# pcb_telemetria_jlcpcb.net
KiCad netlist of a schematic drawn in EAGLE
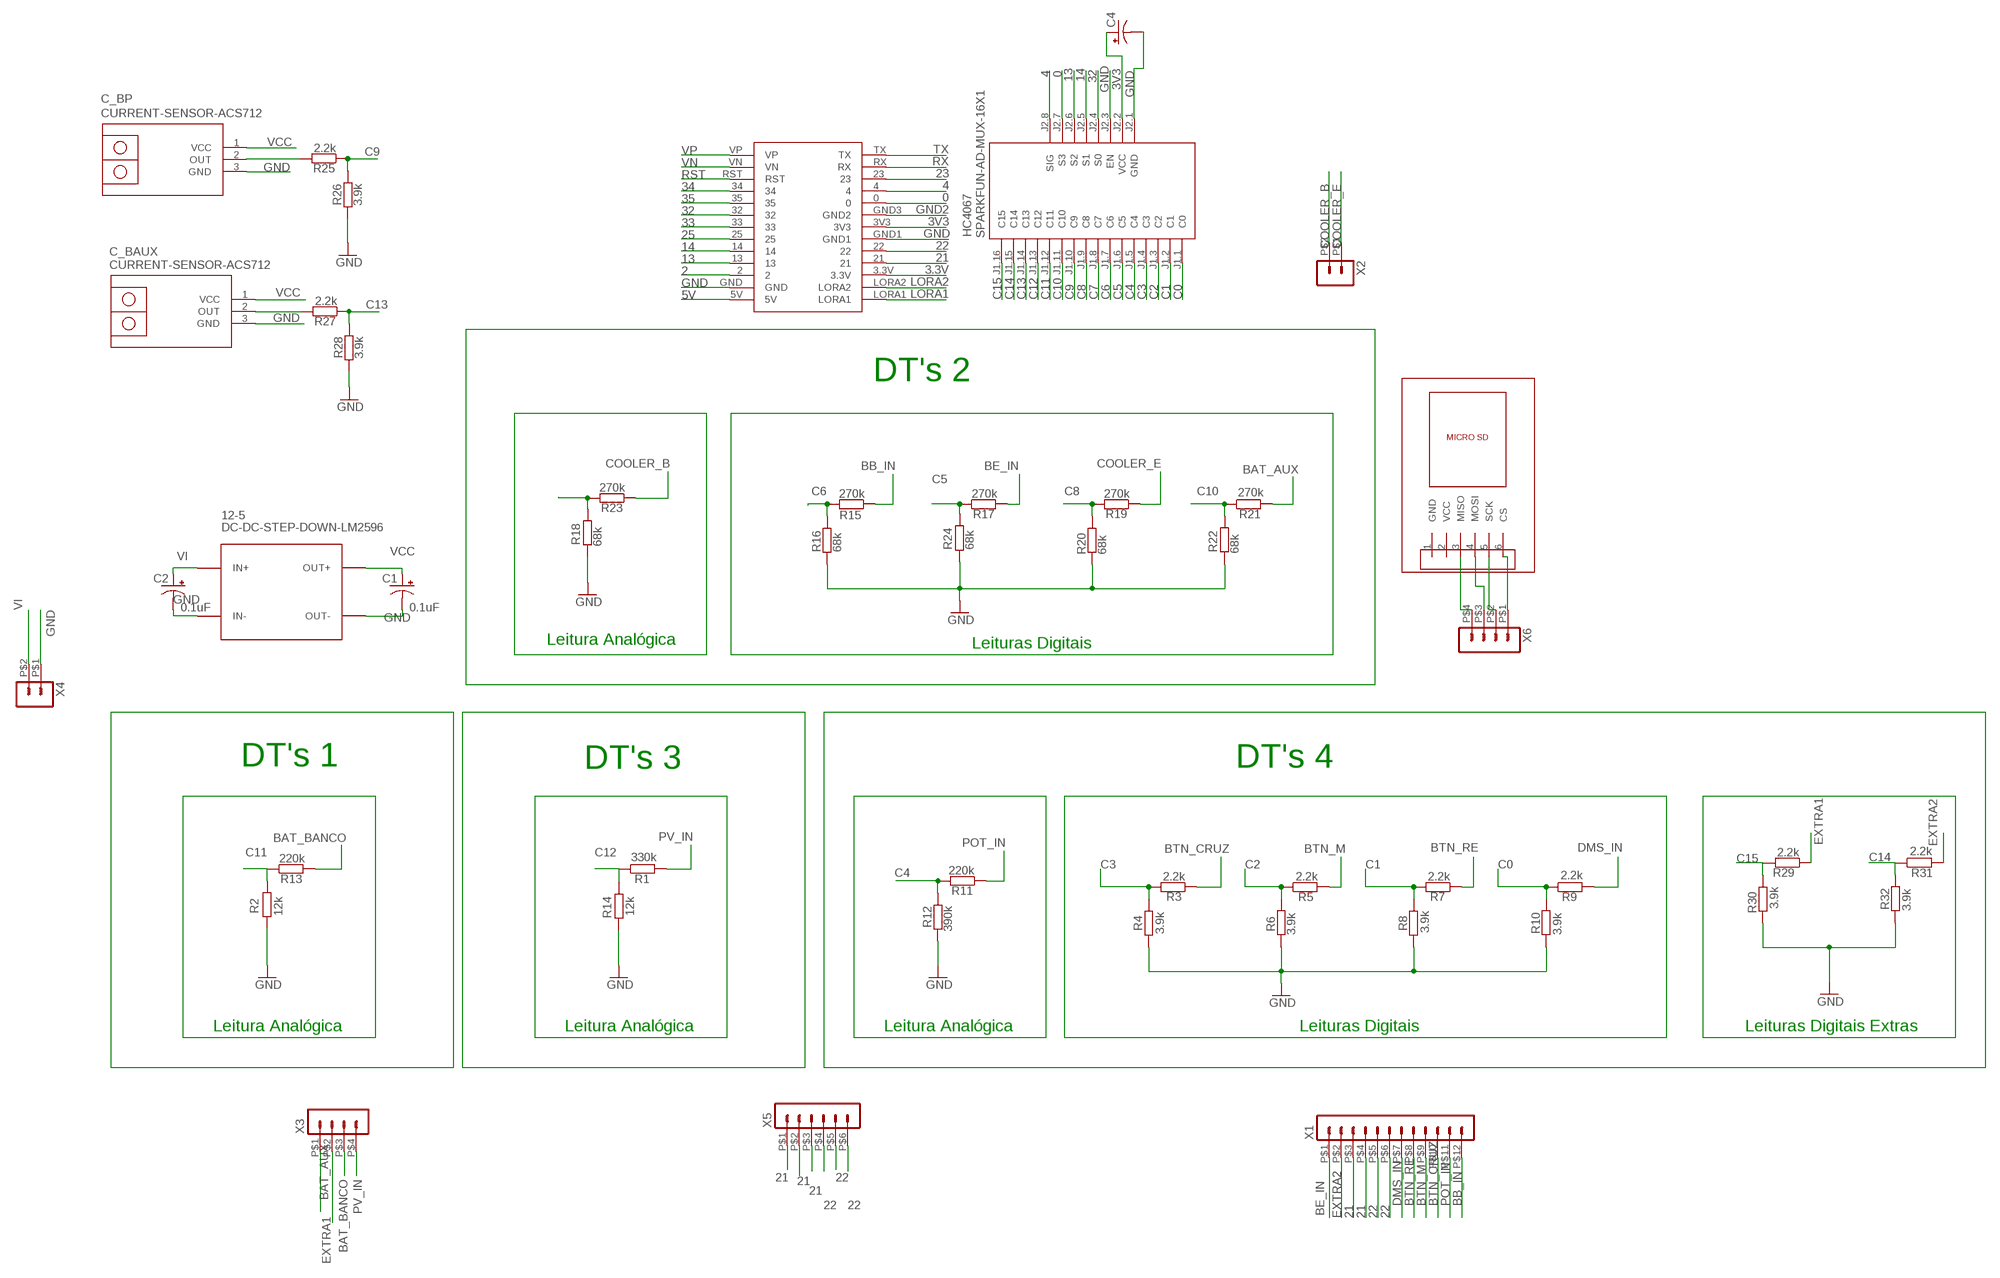
[diagram p0: schematic, sheet 1]

(export (version "E")
  (design (tool "Eeschema 10.0.6"))
  (components
    (comp (ref "12-5")
      (value "DC-DC-STEP-DOWN-LM2596")
      (footprint "eagle-import:DC-DC-STEP-DOWN-LM2596")
      (libsource (lib "eagle-import") (part "DC-DC-STEP-DOWN-LM2596"))
    )
    (comp (ref "C1")
      (value "0.1uF")
      (footprint "eagle-import:E5-5")
      (libsource (lib "eagle-import") (part "CPOL-USE5-5"))
    )
    (comp (ref "C2")
      (value "0.1uF")
      (footprint "eagle-import:E5-5")
      (libsource (lib "eagle-import") (part "CPOL-USE5-5"))
    )
    (comp (ref "C4")
      (value "CPOL-USE5-5")
      (footprint "eagle-import:E5-5")
      (libsource (lib "eagle-import") (part "CPOL-USE5-5"))
    )
    (comp (ref "C_BAUX")
      (value "CURRENT-SENSOR-ACS712")
      (footprint "eagle-import:CURRENT-SENSOR-ACS712")
      (libsource (lib "eagle-import") (part "CURRENT-SENSOR-ACS712"))
    )
    (comp (ref "C_BP")
      (value "CURRENT-SENSOR-ACS712")
      (footprint "eagle-import:CURRENT-SENSOR-ACS712")
      (libsource (lib "eagle-import") (part "CURRENT-SENSOR-ACS712"))
    )
    (comp (ref "HC4067")
      (value "SPARKFUN-AD-MUX-16X1")
      (footprint "eagle-import:SPARKFUN-AD-MUX-16X1")
      (libsource (lib "eagle-import") (part "SPARKFUN-AD-MUX-16X1"))
    )
    (comp (ref "R1")
      (value "330k")
      (footprint "eagle-import:0204_7")
      (libsource (lib "eagle-import") (part "R-EU_0204/7"))
    )
    (comp (ref "R2")
      (value "12k")
      (footprint "eagle-import:0204_7")
      (libsource (lib "eagle-import") (part "R-EU_0204/7"))
    )
    (comp (ref "R3")
      (value "2.2k")
      (footprint "eagle-import:0204_7")
      (libsource (lib "eagle-import") (part "R-EU_0204/7"))
    )
    (comp (ref "R4")
      (value "3.9k")
      (footprint "eagle-import:0204_7")
      (libsource (lib "eagle-import") (part "R-EU_0204/7"))
    )
    (comp (ref "R5")
      (value "2.2k")
      (footprint "eagle-import:0204_7")
      (libsource (lib "eagle-import") (part "R-EU_0204/7"))
    )
    (comp (ref "R6")
      (value "3.9k")
      (footprint "eagle-import:0204_7")
      (libsource (lib "eagle-import") (part "R-EU_0204/7"))
    )
    (comp (ref "R7")
      (value "2.2k")
      (footprint "eagle-import:0204_7")
      (libsource (lib "eagle-import") (part "R-EU_0204/7"))
    )
    (comp (ref "R8")
      (value "3.9k")
      (footprint "eagle-import:0204_7")
      (libsource (lib "eagle-import") (part "R-EU_0204/7"))
    )
    (comp (ref "R9")
      (value "2.2k")
      (footprint "eagle-import:0204_7")
      (libsource (lib "eagle-import") (part "R-EU_0204/7"))
    )
    (comp (ref "R10")
      (value "3.9k")
      (footprint "eagle-import:0204_7")
      (libsource (lib "eagle-import") (part "R-EU_0204/7"))
    )
    (comp (ref "R11")
      (value "220k")
      (footprint "eagle-import:0204_7")
      (libsource (lib "eagle-import") (part "R-EU_0204/7"))
    )
    (comp (ref "R12")
      (value "390k")
      (footprint "eagle-import:0204_7")
      (libsource (lib "eagle-import") (part "R-EU_0204/7"))
    )
    (comp (ref "R13")
      (value "220k")
      (footprint "eagle-import:0204_7")
      (libsource (lib "eagle-import") (part "R-EU_0204/7"))
    )
    (comp (ref "R14")
      (value "12k")
      (footprint "eagle-import:0204_7")
      (libsource (lib "eagle-import") (part "R-EU_0204/7"))
    )
    (comp (ref "R15")
      (value "270k")
      (footprint "eagle-import:0204_7")
      (libsource (lib "eagle-import") (part "R-EU_0204/7"))
    )
    (comp (ref "R16")
      (value "68k")
      (footprint "eagle-import:0204_7")
      (libsource (lib "eagle-import") (part "R-EU_0204/7"))
    )
    (comp (ref "R17")
      (value "270k")
      (footprint "eagle-import:0204_7")
      (libsource (lib "eagle-import") (part "R-EU_0204/7"))
    )
    (comp (ref "R18")
      (value "68k")
      (footprint "eagle-import:0204_7")
      (libsource (lib "eagle-import") (part "R-EU_0204/7"))
    )
    (comp (ref "R19")
      (value "270k")
      (footprint "eagle-import:0204_7")
      (libsource (lib "eagle-import") (part "R-EU_0204/7"))
    )
    (comp (ref "R20")
      (value "68k")
      (footprint "eagle-import:0204_7")
      (libsource (lib "eagle-import") (part "R-EU_0204/7"))
    )
    (comp (ref "R21")
      (value "270k")
      (footprint "eagle-import:0204_7")
      (libsource (lib "eagle-import") (part "R-EU_0204/7"))
    )
    (comp (ref "R22")
      (value "68k")
      (footprint "eagle-import:0204_7")
      (libsource (lib "eagle-import") (part "R-EU_0204/7"))
    )
    (comp (ref "R23")
      (value "270k")
      (footprint "eagle-import:0204_7")
      (libsource (lib "eagle-import") (part "R-EU_0204/7"))
    )
    (comp (ref "R24")
      (value "68k")
      (footprint "eagle-import:0204_7")
      (libsource (lib "eagle-import") (part "R-EU_0204/7"))
    )
    (comp (ref "R25")
      (value "2.2k")
      (footprint "eagle-import:0204_7")
      (libsource (lib "eagle-import") (part "R-EU_0204/7"))
    )
    (comp (ref "R26")
      (value "3.9k")
      (footprint "eagle-import:0204_7")
      (libsource (lib "eagle-import") (part "R-EU_0204/7"))
    )
    (comp (ref "R27")
      (value "2.2k")
      (footprint "eagle-import:0204_7")
      (libsource (lib "eagle-import") (part "R-EU_0204/7"))
    )
    (comp (ref "R28")
      (value "3.9k")
      (footprint "eagle-import:0204_7")
      (libsource (lib "eagle-import") (part "R-EU_0204/7"))
    )
    (comp (ref "R29")
      (value "2.2k")
      (footprint "eagle-import:0204_7")
      (libsource (lib "eagle-import") (part "R-EU_0204/7"))
    )
    (comp (ref "R30")
      (value "3.9k")
      (footprint "eagle-import:0204_7")
      (libsource (lib "eagle-import") (part "R-EU_0204/7"))
    )
    (comp (ref "R31")
      (value "2.2k")
      (footprint "eagle-import:0204_7")
      (libsource (lib "eagle-import") (part "R-EU_0204/7"))
    )
    (comp (ref "R32")
      (value "3.9k")
      (footprint "eagle-import:0204_7")
      (libsource (lib "eagle-import") (part "R-EU_0204/7"))
    )
    (comp (ref "U$1")
      (value "TTGOBEAM")
      (footprint "eagle-import:TTGOBEAM")
      (libsource (lib "eagle-import") (part "TTGOBEAM"))
    )
    (comp (ref "U$2")
      (value "MICRO_SD_MODULE")
      (footprint "eagle-import:MICRO_SD")
      (libsource (lib "eagle-import") (part "MICRO_SD_MODULE"))
    )
    (comp (ref "X1")
      (value "HEADER_POS12_43045-1212")
      (footprint "eagle-import:43045-1212")
      (libsource (lib "eagle-import") (part "HEADER_POS12_?43045-1212"))
    )
    (comp (ref "X2")
      (value "HEADER_POS2_43045-0212")
      (footprint "eagle-import:43045-0212")
      (libsource (lib "eagle-import") (part "HEADER_POS2_?43045-0212"))
    )
    (comp (ref "X3")
      (value "HEADER_POS4_43045-0412")
      (footprint "eagle-import:43045-0412")
      (libsource (lib "eagle-import") (part "HEADER_POS4_?43045-0412"))
    )
    (comp (ref "X4")
      (value "HEADER_POS2_43045-0212")
      (footprint "eagle-import:43045-0212")
      (libsource (lib "eagle-import") (part "HEADER_POS2_?43045-0212"))
    )
    (comp (ref "X5")
      (value "HEADER_POS6_43045-0612")
      (footprint "eagle-import:43045-0612")
      (libsource (lib "eagle-import") (part "HEADER_POS6_?43045-0612"))
    )
    (comp (ref "X6")
      (value "HEADER_POS4_43045-0412")
      (footprint "eagle-import:43045-0412")
      (libsource (lib "eagle-import") (part "HEADER_POS4_?43045-0412"))
    )
  )
  (nets
    (net (code "1") (name "/0") (class "Default")
      (node (ref "HC4067") (pin "J2.7") (pinfunction "S3_J2.7") (pintype "bidirectional"))
      (node (ref "U$1") (pin "0") (pinfunction "0_0") (pintype "bidirectional"))
    )
    (net (code "2") (name "/2") (class "Default")
      (node (ref "U$1") (pin "2") (pinfunction "2_2") (pintype "bidirectional"))
    )
    (net (code "3") (name "/3.3V") (class "Default")
      (node (ref "U$1") (pin "3.3V") (pinfunction "3.3V_3.3V") (pintype "bidirectional"))
    )
    (net (code "4") (name "/3V3") (class "Default")
      (node (ref "C4") (pin "+") (pinfunction "+_+") (pintype "passive"))
      (node (ref "HC4067") (pin "J2.2") (pinfunction "VCC_J2.2") (pintype "power_in"))
      (node (ref "U$1") (pin "3V3") (pinfunction "3V3_3V3") (pintype "bidirectional"))
    )
    (net (code "5") (name "/4") (class "Default")
      (node (ref "HC4067") (pin "J2.8") (pinfunction "SIG_J2.8") (pintype "bidirectional"))
      (node (ref "U$1") (pin "4") (pinfunction "4_4") (pintype "bidirectional"))
    )
    (net (code "6") (name "/5V") (class "Default")
      (node (ref "U$1") (pin "5V") (pinfunction "5V_5V") (pintype "bidirectional"))
    )
    (net (code "7") (name "/13") (class "Default")
      (node (ref "HC4067") (pin "J2.6") (pinfunction "S2_J2.6") (pintype "bidirectional"))
      (node (ref "U$1") (pin "13") (pinfunction "13_13") (pintype "bidirectional"))
    )
    (net (code "8") (name "/14") (class "Default")
      (node (ref "HC4067") (pin "J2.5") (pinfunction "S1_J2.5") (pintype "bidirectional"))
      (node (ref "U$1") (pin "14") (pinfunction "14_14") (pintype "bidirectional"))
    )
    (net (code "9") (name "/21") (class "Default")
      (node (ref "U$1") (pin "21") (pinfunction "21_21") (pintype "bidirectional"))
      (node (ref "X1") (pin "P$3") (pinfunction "3_P$3") (pintype "passive"))
      (node (ref "X1") (pin "P$4") (pinfunction "4_P$4") (pintype "passive"))
      (node (ref "X5") (pin "P$1") (pinfunction "1_P$1") (pintype "passive"))
      (node (ref "X5") (pin "P$2") (pinfunction "2_P$2") (pintype "passive"))
      (node (ref "X5") (pin "P$3") (pinfunction "3_P$3") (pintype "passive"))
    )
    (net (code "10") (name "/22") (class "Default")
      (node (ref "U$1") (pin "22") (pinfunction "22_22") (pintype "bidirectional"))
      (node (ref "X1") (pin "P$5") (pinfunction "5_P$5") (pintype "passive"))
      (node (ref "X1") (pin "P$6") (pinfunction "6_P$6") (pintype "passive"))
      (node (ref "X5") (pin "P$4") (pinfunction "4_P$4") (pintype "passive"))
      (node (ref "X5") (pin "P$5") (pinfunction "5_P$5") (pintype "passive"))
      (node (ref "X5") (pin "P$6") (pinfunction "6_P$6") (pintype "passive"))
    )
    (net (code "11") (name "/23") (class "Default")
      (node (ref "U$1") (pin "23") (pinfunction "23_23") (pintype "bidirectional"))
    )
    (net (code "12") (name "/25") (class "Default")
      (node (ref "U$1") (pin "25") (pinfunction "25_25") (pintype "bidirectional"))
    )
    (net (code "13") (name "/32") (class "Default")
      (node (ref "HC4067") (pin "J2.4") (pinfunction "S0_J2.4") (pintype "bidirectional"))
      (node (ref "U$1") (pin "32") (pinfunction "32_32") (pintype "bidirectional"))
    )
    (net (code "14") (name "/33") (class "Default")
      (node (ref "U$1") (pin "33") (pinfunction "33_33") (pintype "bidirectional"))
    )
    (net (code "15") (name "/34") (class "Default")
      (node (ref "U$1") (pin "34") (pinfunction "34_34") (pintype "bidirectional"))
    )
    (net (code "16") (name "/35") (class "Default")
      (node (ref "U$1") (pin "35") (pinfunction "35_35") (pintype "bidirectional"))
    )
    (net (code "17") (name "/BAT_AUX") (class "Default")
      (node (ref "R21") (pin "2") (pinfunction "2_2") (pintype "passive"))
      (node (ref "X3") (pin "P$1") (pinfunction "1_P$1") (pintype "passive"))
    )
    (net (code "18") (name "/BAT_BANCO") (class "Default")
      (node (ref "R13") (pin "2") (pinfunction "2_2") (pintype "passive"))
      (node (ref "X3") (pin "P$3") (pinfunction "3_P$3") (pintype "passive"))
    )
    (net (code "19") (name "/BB_IN") (class "Default")
      (node (ref "R15") (pin "1") (pinfunction "1_1") (pintype "passive"))
      (node (ref "X1") (pin "P$12") (pinfunction "12_P$12") (pintype "passive"))
    )
    (net (code "20") (name "/BE_IN") (class "Default")
      (node (ref "R17") (pin "2") (pinfunction "2_2") (pintype "passive"))
      (node (ref "X1") (pin "P$1") (pinfunction "1_P$1") (pintype "passive"))
    )
    (net (code "21") (name "/BTN_CRUZ") (class "Default")
      (node (ref "R3") (pin "1") (pinfunction "1_1") (pintype "passive"))
      (node (ref "X1") (pin "P$10") (pinfunction "10_P$10") (pintype "passive"))
    )
    (net (code "22") (name "/BTN_M") (class "Default")
      (node (ref "R5") (pin "2") (pinfunction "2_2") (pintype "passive"))
      (node (ref "X1") (pin "P$9") (pinfunction "9_P$9") (pintype "passive"))
    )
    (net (code "23") (name "/BTN_RE") (class "Default")
      (node (ref "R7") (pin "1") (pinfunction "1_1") (pintype "passive"))
      (node (ref "X1") (pin "P$8") (pinfunction "8_P$8") (pintype "passive"))
    )
    (net (code "24") (name "/C0") (class "Default")
      (node (ref "HC4067") (pin "J1.1") (pinfunction "C0_J1.1") (pintype "bidirectional"))
      (node (ref "R10") (pin "2") (pinfunction "2_2") (pintype "passive"))
      (node (ref "R9") (pin "1") (pinfunction "1_1") (pintype "passive"))
    )
    (net (code "25") (name "/C1") (class "Default")
      (node (ref "HC4067") (pin "J1.2") (pinfunction "C1_J1.2") (pintype "bidirectional"))
      (node (ref "R7") (pin "2") (pinfunction "2_2") (pintype "passive"))
      (node (ref "R8") (pin "1") (pinfunction "1_1") (pintype "passive"))
    )
    (net (code "26") (name "/C2") (class "Default")
      (node (ref "HC4067") (pin "J1.3") (pinfunction "C2_J1.3") (pintype "bidirectional"))
      (node (ref "R5") (pin "1") (pinfunction "1_1") (pintype "passive"))
      (node (ref "R6") (pin "2") (pinfunction "2_2") (pintype "passive"))
    )
    (net (code "27") (name "/C3") (class "Default")
      (node (ref "HC4067") (pin "J1.4") (pinfunction "C3_J1.4") (pintype "bidirectional"))
      (node (ref "R3") (pin "2") (pinfunction "2_2") (pintype "passive"))
      (node (ref "R4") (pin "1") (pinfunction "1_1") (pintype "passive"))
    )
    (net (code "28") (name "/C4") (class "Default")
      (node (ref "HC4067") (pin "J1.5") (pinfunction "C4_J1.5") (pintype "bidirectional"))
      (node (ref "R11") (pin "2") (pinfunction "2_2") (pintype "passive"))
      (node (ref "R12") (pin "1") (pinfunction "1_1") (pintype "passive"))
    )
    (net (code "29") (name "/C5") (class "Default")
      (node (ref "HC4067") (pin "J1.6") (pinfunction "C5_J1.6") (pintype "bidirectional"))
      (node (ref "R17") (pin "1") (pinfunction "1_1") (pintype "passive"))
      (node (ref "R24") (pin "1") (pinfunction "1_1") (pintype "passive"))
    )
    (net (code "30") (name "/C6") (class "Default")
      (node (ref "HC4067") (pin "J1.7") (pinfunction "C6_J1.7") (pintype "bidirectional"))
      (node (ref "R15") (pin "2") (pinfunction "2_2") (pintype "passive"))
      (node (ref "R16") (pin "1") (pinfunction "1_1") (pintype "passive"))
    )
    (net (code "31") (name "/C7") (class "Default")
      (node (ref "HC4067") (pin "J1.8") (pinfunction "C7_J1.8") (pintype "bidirectional"))
      (node (ref "R18") (pin "2") (pinfunction "2_2") (pintype "passive"))
      (node (ref "R23") (pin "2") (pinfunction "2_2") (pintype "passive"))
    )
    (net (code "32") (name "/C8") (class "Default")
      (node (ref "HC4067") (pin "J1.9") (pinfunction "C8_J1.9") (pintype "bidirectional"))
      (node (ref "R19") (pin "2") (pinfunction "2_2") (pintype "passive"))
      (node (ref "R20") (pin "1") (pinfunction "1_1") (pintype "passive"))
    )
    (net (code "33") (name "/C9") (class "Default")
      (node (ref "HC4067") (pin "J1.10") (pinfunction "C9_J1.10") (pintype "bidirectional"))
      (node (ref "R25") (pin "1") (pinfunction "1_1") (pintype "passive"))
      (node (ref "R26") (pin "1") (pinfunction "1_1") (pintype "passive"))
    )
    (net (code "34") (name "/C10") (class "Default")
      (node (ref "HC4067") (pin "J1.11") (pinfunction "C10_J1.11") (pintype "bidirectional"))
      (node (ref "R21") (pin "1") (pinfunction "1_1") (pintype "passive"))
      (node (ref "R22") (pin "2") (pinfunction "2_2") (pintype "passive"))
    )
    (net (code "35") (name "/C11") (class "Default")
      (node (ref "HC4067") (pin "J1.12") (pinfunction "C11_J1.12") (pintype "bidirectional"))
      (node (ref "R13") (pin "1") (pinfunction "1_1") (pintype "passive"))
      (node (ref "R2") (pin "2") (pinfunction "2_2") (pintype "passive"))
    )
    (net (code "36") (name "/C12") (class "Default")
      (node (ref "HC4067") (pin "J1.13") (pinfunction "C12_J1.13") (pintype "bidirectional"))
      (node (ref "R1") (pin "1") (pinfunction "1_1") (pintype "passive"))
      (node (ref "R14") (pin "2") (pinfunction "2_2") (pintype "passive"))
    )
    (net (code "37") (name "/C13") (class "Default")
      (node (ref "HC4067") (pin "J1.14") (pinfunction "C13_J1.14") (pintype "bidirectional"))
      (node (ref "R27") (pin "1") (pinfunction "1_1") (pintype "passive"))
      (node (ref "R28") (pin "1") (pinfunction "1_1") (pintype "passive"))
    )
    (net (code "38") (name "/C14") (class "Default")
      (node (ref "HC4067") (pin "J1.15") (pinfunction "C14_J1.15") (pintype "bidirectional"))
      (node (ref "R31") (pin "1") (pinfunction "1_1") (pintype "passive"))
      (node (ref "R32") (pin "2") (pinfunction "2_2") (pintype "passive"))
    )
    (net (code "39") (name "/C15") (class "Default")
      (node (ref "HC4067") (pin "J1.16") (pinfunction "C15_J1.16") (pintype "bidirectional"))
      (node (ref "R29") (pin "2") (pinfunction "2_2") (pintype "passive"))
      (node (ref "R30") (pin "1") (pinfunction "1_1") (pintype "passive"))
    )
    (net (code "40") (name "/COOLER_B") (class "Default")
      (node (ref "R23") (pin "1") (pinfunction "1_1") (pintype "passive"))
      (node (ref "X2") (pin "P$2") (pinfunction "2_P$2") (pintype "passive"))
    )
    (net (code "41") (name "/COOLER_E") (class "Default")
      (node (ref "R19") (pin "1") (pinfunction "1_1") (pintype "passive"))
      (node (ref "X2") (pin "P$1") (pinfunction "1_P$1") (pintype "passive"))
    )
    (net (code "42") (name "/DMS_IN") (class "Default")
      (node (ref "R9") (pin "2") (pinfunction "2_2") (pintype "passive"))
      (node (ref "X1") (pin "P$7") (pinfunction "7_P$7") (pintype "passive"))
    )
    (net (code "43") (name "/EXTRA1") (class "Default")
      (node (ref "R29") (pin "1") (pinfunction "1_1") (pintype "passive"))
      (node (ref "X3") (pin "P$2") (pinfunction "2_P$2") (pintype "passive"))
    )
    (net (code "44") (name "/EXTRA2") (class "Default")
      (node (ref "R31") (pin "2") (pinfunction "2_2") (pintype "passive"))
      (node (ref "X1") (pin "P$2") (pinfunction "2_P$2") (pintype "passive"))
    )
    (net (code "45") (name "/GND2") (class "Default")
      (node (ref "U$1") (pin "GND3") (pinfunction "GND2_GND3") (pintype "bidirectional"))
    )
    (net (code "46") (name "/LORA1") (class "Default")
      (node (ref "U$1") (pin "LORA1") (pinfunction "LORA1_LORA1") (pintype "bidirectional"))
    )
    (net (code "47") (name "/LORA2") (class "Default")
      (node (ref "U$1") (pin "LORA2") (pinfunction "LORA2_LORA2") (pintype "bidirectional"))
    )
    (net (code "48") (name "/POT_IN") (class "Default")
      (node (ref "R11") (pin "1") (pinfunction "1_1") (pintype "passive"))
      (node (ref "X1") (pin "P$11") (pinfunction "11_P$11") (pintype "passive"))
    )
    (net (code "49") (name "/PV_IN") (class "Default")
      (node (ref "R1") (pin "2") (pinfunction "2_2") (pintype "passive"))
      (node (ref "X3") (pin "P$4") (pinfunction "4_P$4") (pintype "passive"))
    )
    (net (code "50") (name "/RST") (class "Default")
      (node (ref "U$1") (pin "RST") (pinfunction "RST_RST") (pintype "bidirectional"))
    )
    (net (code "51") (name "/RX") (class "Default")
      (node (ref "U$1") (pin "RX") (pinfunction "RX_RX") (pintype "bidirectional"))
    )
    (net (code "52") (name "/TX") (class "Default")
      (node (ref "U$1") (pin "TX") (pinfunction "TX_TX") (pintype "bidirectional"))
    )
    (net (code "53") (name "/VCC") (class "Default")
      (node (ref "12-5") (pin "OUT+") (pinfunction "OUT+_OUT+") (pintype "bidirectional"))
      (node (ref "C1") (pin "+") (pinfunction "+_+") (pintype "passive"))
      (node (ref "C_BAUX") (pin "1") (pinfunction "VCC_1") (pintype "power_in"))
      (node (ref "C_BP") (pin "1") (pinfunction "VCC_1") (pintype "power_in"))
    )
    (net (code "54") (name "/VI") (class "Default")
      (node (ref "12-5") (pin "IN+") (pinfunction "IN+_IN+") (pintype "bidirectional"))
      (node (ref "C2") (pin "+") (pinfunction "+_+") (pintype "passive"))
      (node (ref "X4") (pin "P$2") (pinfunction "2_P$2") (pintype "passive"))
    )
    (net (code "55") (name "/VN") (class "Default")
      (node (ref "U$1") (pin "VN") (pinfunction "VN_VN") (pintype "bidirectional"))
    )
    (net (code "56") (name "/VP") (class "Default")
      (node (ref "U$1") (pin "VP") (pinfunction "VP_VP") (pintype "bidirectional"))
    )
    (net (code "57") (name "GND") (class "Default")
      (node (ref "12-5") (pin "IN-") (pinfunction "IN-_IN-") (pintype "bidirectional"))
      (node (ref "12-5") (pin "OUT-") (pinfunction "OUT-_OUT-") (pintype "bidirectional"))
      (node (ref "C1") (pin "-") (pinfunction "-_-") (pintype "passive"))
      (node (ref "C2") (pin "-") (pinfunction "-_-") (pintype "passive"))
      (node (ref "C4") (pin "-") (pinfunction "-_-") (pintype "passive"))
      (node (ref "C_BAUX") (pin "3") (pinfunction "GND_3") (pintype "power_in"))
      (node (ref "C_BP") (pin "3") (pinfunction "GND_3") (pintype "power_in"))
      (node (ref "HC4067") (pin "J2.1") (pinfunction "GND_J2.1") (pintype "power_in"))
      (node (ref "HC4067") (pin "J2.3") (pinfunction "EN_J2.3") (pintype "input"))
      (node (ref "R10") (pin "1") (pinfunction "1_1") (pintype "passive"))
      (node (ref "R12") (pin "2") (pinfunction "2_2") (pintype "passive"))
      (node (ref "R14") (pin "1") (pinfunction "1_1") (pintype "passive"))
      (node (ref "R16") (pin "2") (pinfunction "2_2") (pintype "passive"))
      (node (ref "R18") (pin "1") (pinfunction "1_1") (pintype "passive"))
      (node (ref "R2") (pin "1") (pinfunction "1_1") (pintype "passive"))
      (node (ref "R20") (pin "2") (pinfunction "2_2") (pintype "passive"))
      (node (ref "R22") (pin "1") (pinfunction "1_1") (pintype "passive"))
      (node (ref "R26") (pin "2") (pinfunction "2_2") (pintype "passive"))
      (node (ref "R28") (pin "2") (pinfunction "2_2") (pintype "passive"))
      (node (ref "R30") (pin "2") (pinfunction "2_2") (pintype "passive"))
      (node (ref "R32") (pin "1") (pinfunction "1_1") (pintype "passive"))
      (node (ref "R4") (pin "2") (pinfunction "2_2") (pintype "passive"))
      (node (ref "R6") (pin "1") (pinfunction "1_1") (pintype "passive"))
      (node (ref "R8") (pin "2") (pinfunction "2_2") (pintype "passive"))
      (node (ref "U$1") (pin "GND") (pinfunction "GND_GND") (pintype "bidirectional"))
      (node (ref "U$1") (pin "GND1") (pinfunction "GND1_GND1") (pintype "bidirectional"))
      (node (ref "X4") (pin "P$1") (pinfunction "1_P$1") (pintype "passive"))
    )
    (net (code "58") (name "Net-(C_BAUX-OUT)") (class "Default")
      (node (ref "C_BAUX") (pin "2") (pinfunction "OUT_2") (pintype "output"))
      (node (ref "R27") (pin "2") (pinfunction "2_2") (pintype "passive"))
    )
    (net (code "59") (name "Net-(C_BP-OUT)") (class "Default")
      (node (ref "C_BP") (pin "2") (pinfunction "OUT_2") (pintype "output"))
      (node (ref "R25") (pin "2") (pinfunction "2_2") (pintype "passive"))
    )
    (net (code "60") (name "Net-(U$2-CS)") (class "Default")
      (node (ref "U$2") (pin "6") (pinfunction "CS_6") (pintype "input"))
      (node (ref "X6") (pin "P$1") (pinfunction "1_P$1") (pintype "passive"))
    )
    (net (code "61") (name "Net-(U$2-MISO)") (class "Default")
      (node (ref "U$2") (pin "3") (pinfunction "MISO_3") (pintype "bidirectional"))
      (node (ref "X6") (pin "P$4") (pinfunction "4_P$4") (pintype "passive"))
    )
    (net (code "62") (name "Net-(U$2-MOSI)") (class "Default")
      (node (ref "U$2") (pin "4") (pinfunction "MOSI_4") (pintype "bidirectional"))
      (node (ref "X6") (pin "P$3") (pinfunction "3_P$3") (pintype "passive"))
    )
    (net (code "63") (name "Net-(U$2-SCK)") (class "Default")
      (node (ref "U$2") (pin "5") (pinfunction "SCK_5") (pintype "input"))
      (node (ref "X6") (pin "P$2") (pinfunction "2_P$2") (pintype "passive"))
    )
    (net (code "64") (name "unconnected-(R24-Pad2)") (class "Default")
      (node (ref "R24") (pin "2") (pinfunction "2_2") (pintype "passive"))
    )
    (net (code "65") (name "unconnected-(U$2-GND-Pad1)") (class "Default")
      (node (ref "U$2") (pin "1") (pinfunction "GND_1") (pintype "bidirectional"))
    )
    (net (code "66") (name "unconnected-(U$2-VCC-Pad2)") (class "Default")
      (node (ref "U$2") (pin "2") (pinfunction "VCC_2") (pintype "bidirectional"))
    )
  )
)
